# BG95_RF.net
KiCad netlist of a schematic drawn in Altium Designer
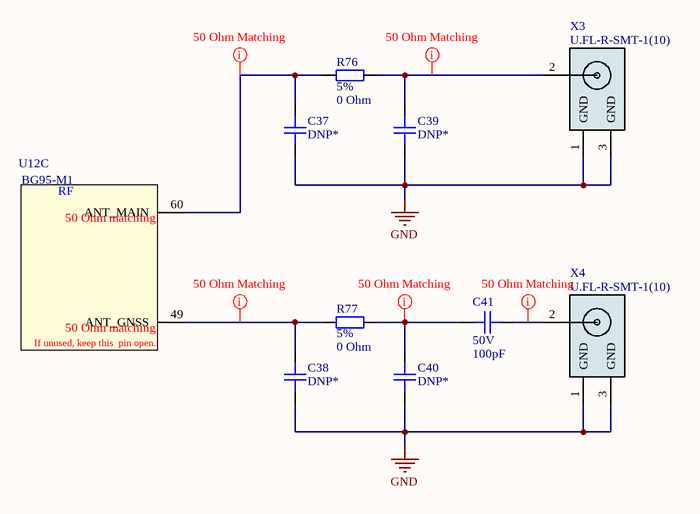
[diagram p0: BG95_RF.SchDoc]

(export (version "E")
  (design (tool "Eeschema 10.0.6"))
  (components
    (comp (ref "C37")
      (value "DNP*")
      (footprint "C0402")
      (description "Placeholder for a 0402 capacitor")
      (libsource (lib "capacitors_smd") (part "CAP CER NO_BOM 0402"))
    )
    (comp (ref "C38")
      (value "DNP*")
      (footprint "C0402")
      (description "Placeholder for a 0402 capacitor")
      (libsource (lib "capacitors_smd") (part "CAP CER NO_BOM 0402"))
    )
    (comp (ref "C39")
      (value "DNP*")
      (footprint "C0402")
      (description "Placeholder for a 0402 capacitor")
      (libsource (lib "capacitors_smd") (part "CAP CER NO_BOM 0402"))
    )
    (comp (ref "C40")
      (value "DNP*")
      (footprint "C0402")
      (description "Placeholder for a 0402 capacitor")
      (libsource (lib "capacitors_smd") (part "CAP CER NO_BOM 0402"))
    )
    (comp (ref "C41")
      (value "C 100pF 50V C0G, NP0 0402")
      (footprint "C0402")
      (description "100pF ±5% 50V Ceramic Capacitor C0G, NP0 0402 (1005 Metric)")
      (fields
        (field (name "MANUFACTURER") "Yageo")
        (field (name "MANUFACTURER PART NUMBER") "CC0402JRNPO9BN101")
        (field (name "VOLTAGE") "50V")
        (field (name "CAPACITANCE") "100pF")
      )
      (libsource (lib "capacitors_smd") (part "C 100pF 50V C0G, NP0 0402"))
    )
    (comp (ref "R76")
      (value "RES SMD 0 OHM JUMPER 1/16W 0402")
      (footprint "R0402")
      (description "0 Ohms Jumper 0.063W, 1/16W Chip Resistor 0402 (1005 Metric) Moisture Resistant Thick Film")
      (fields
        (field (name "MANUFACTURER") "Yageo")
        (field (name "MANUFACTURER PART NUMBER") "RC0402JR-070RL")
        (field (name "TOLERANCE") "5%")
        (field (name "RESISTANCE") "0 Ohm")
      )
      (libsource (lib "resistors_smd") (part "RES SMD 0 OHM JUMPER 1/16W 0402"))
    )
    (comp (ref "R77")
      (value "RES SMD 0 OHM JUMPER 1/16W 0402")
      (footprint "R0402")
      (description "0 Ohms Jumper 0.063W, 1/16W Chip Resistor 0402 (1005 Metric) Moisture Resistant Thick Film")
      (fields
        (field (name "MANUFACTURER") "Yageo")
        (field (name "MANUFACTURER PART NUMBER") "RC0402JR-070RL")
        (field (name "TOLERANCE") "5%")
        (field (name "RESISTANCE") "0 Ohm")
      )
      (libsource (lib "resistors_smd") (part "RES SMD 0 OHM JUMPER 1/16W 0402"))
    )
    (comp (ref "U12")
      (value "BG95-M1")
      (footprint "BG95")
      (description "LTE Cat M1, LTE Cat NB2 and EGPRS Transceiver Module Antenna Not Included Surface Mount")
      (fields (field (name "MANUFACTURER") "QUECTEL"))
      (libsource (lib "BLDC_Motor_Driver") (part "MOD BG95 RX TXRX CELLULAR LTE/NAV SMD"))
    )
    (comp (ref "X3")
      (value "U.FL-R-SMT-1(10)")
      (footprint "CONN U.FL RCPT STR 50 OHM SMD")
      (description "U.FL (UMCC) Connector Receptacle, Male Pin 50Ohm Surface Mount Solder")
      (fields (field (name "MANUFACTURER") "Hirose"))
      (libsource (lib "RelibondHMI") (part "CONN U.FL RCPT STR 50 OHM SMD"))
    )
    (comp (ref "X4")
      (value "U.FL-R-SMT-1(10)")
      (footprint "CONN U.FL RCPT STR 50 OHM SMD")
      (description "U.FL (UMCC) Connector Receptacle, Male Pin 50Ohm Surface Mount Solder")
      (fields (field (name "MANUFACTURER") "Hirose"))
      (libsource (lib "RelibondHMI") (part "CONN U.FL RCPT STR 50 OHM SMD"))
    )
  )
  (nets
    (net (code "1") (name "GND") (class "Default")
      (node (ref "C37") (pin "1") (pinfunction "1_1") (pintype "passive"))
      (node (ref "C38") (pin "1") (pinfunction "1_1") (pintype "passive"))
      (node (ref "C39") (pin "1") (pinfunction "1_1") (pintype "passive"))
      (node (ref "C40") (pin "1") (pinfunction "1_1") (pintype "passive"))
      (node (ref "X3") (pin "1") (pinfunction "GND_1") (pintype "passive"))
      (node (ref "X3") (pin "3") (pinfunction "GND_3") (pintype "passive"))
      (node (ref "X4") (pin "1") (pinfunction "GND_1") (pintype "passive"))
      (node (ref "X4") (pin "3") (pinfunction "GND_3") (pintype "passive"))
    )
    (net (code "2") (name "Net-(C40-Pad2)") (class "Default")
      (node (ref "C40") (pin "2") (pinfunction "2_2") (pintype "passive"))
      (node (ref "C41") (pin "1") (pinfunction "1_1") (pintype "passive"))
      (node (ref "R77") (pin "2") (pinfunction "2_2") (pintype "passive"))
    )
    (net (code "3") (name "Net-(U12C-ANT_GNSS)") (class "Default")
      (node (ref "C38") (pin "2") (pinfunction "2_2") (pintype "passive"))
      (node (ref "R77") (pin "1") (pinfunction "1_1") (pintype "passive"))
      (node (ref "U12") (pin "49") (pinfunction "ANT_GNSS_49") (pintype "passive"))
    )
    (net (code "4") (name "Net-(U12C-ANT_MAIN)") (class "Default")
      (node (ref "C37") (pin "2") (pinfunction "2_2") (pintype "passive"))
      (node (ref "R76") (pin "1") (pinfunction "1_1") (pintype "passive"))
      (node (ref "U12") (pin "60") (pinfunction "ANT_MAIN_60") (pintype "passive"))
    )
    (net (code "5") (name "Net-(X3-Signal)") (class "Default")
      (node (ref "C39") (pin "2") (pinfunction "2_2") (pintype "passive"))
      (node (ref "R76") (pin "2") (pinfunction "2_2") (pintype "passive"))
      (node (ref "X3") (pin "2") (pinfunction "Signal_2") (pintype "passive"))
    )
    (net (code "6") (name "Net-(X4-Signal)") (class "Default")
      (node (ref "C41") (pin "2") (pinfunction "2_2") (pintype "passive"))
      (node (ref "X4") (pin "2") (pinfunction "Signal_2") (pintype "passive"))
    )
  )
)
